# shield_radio-comand.net
KiCad netlist of a schematic drawn in EAGLE
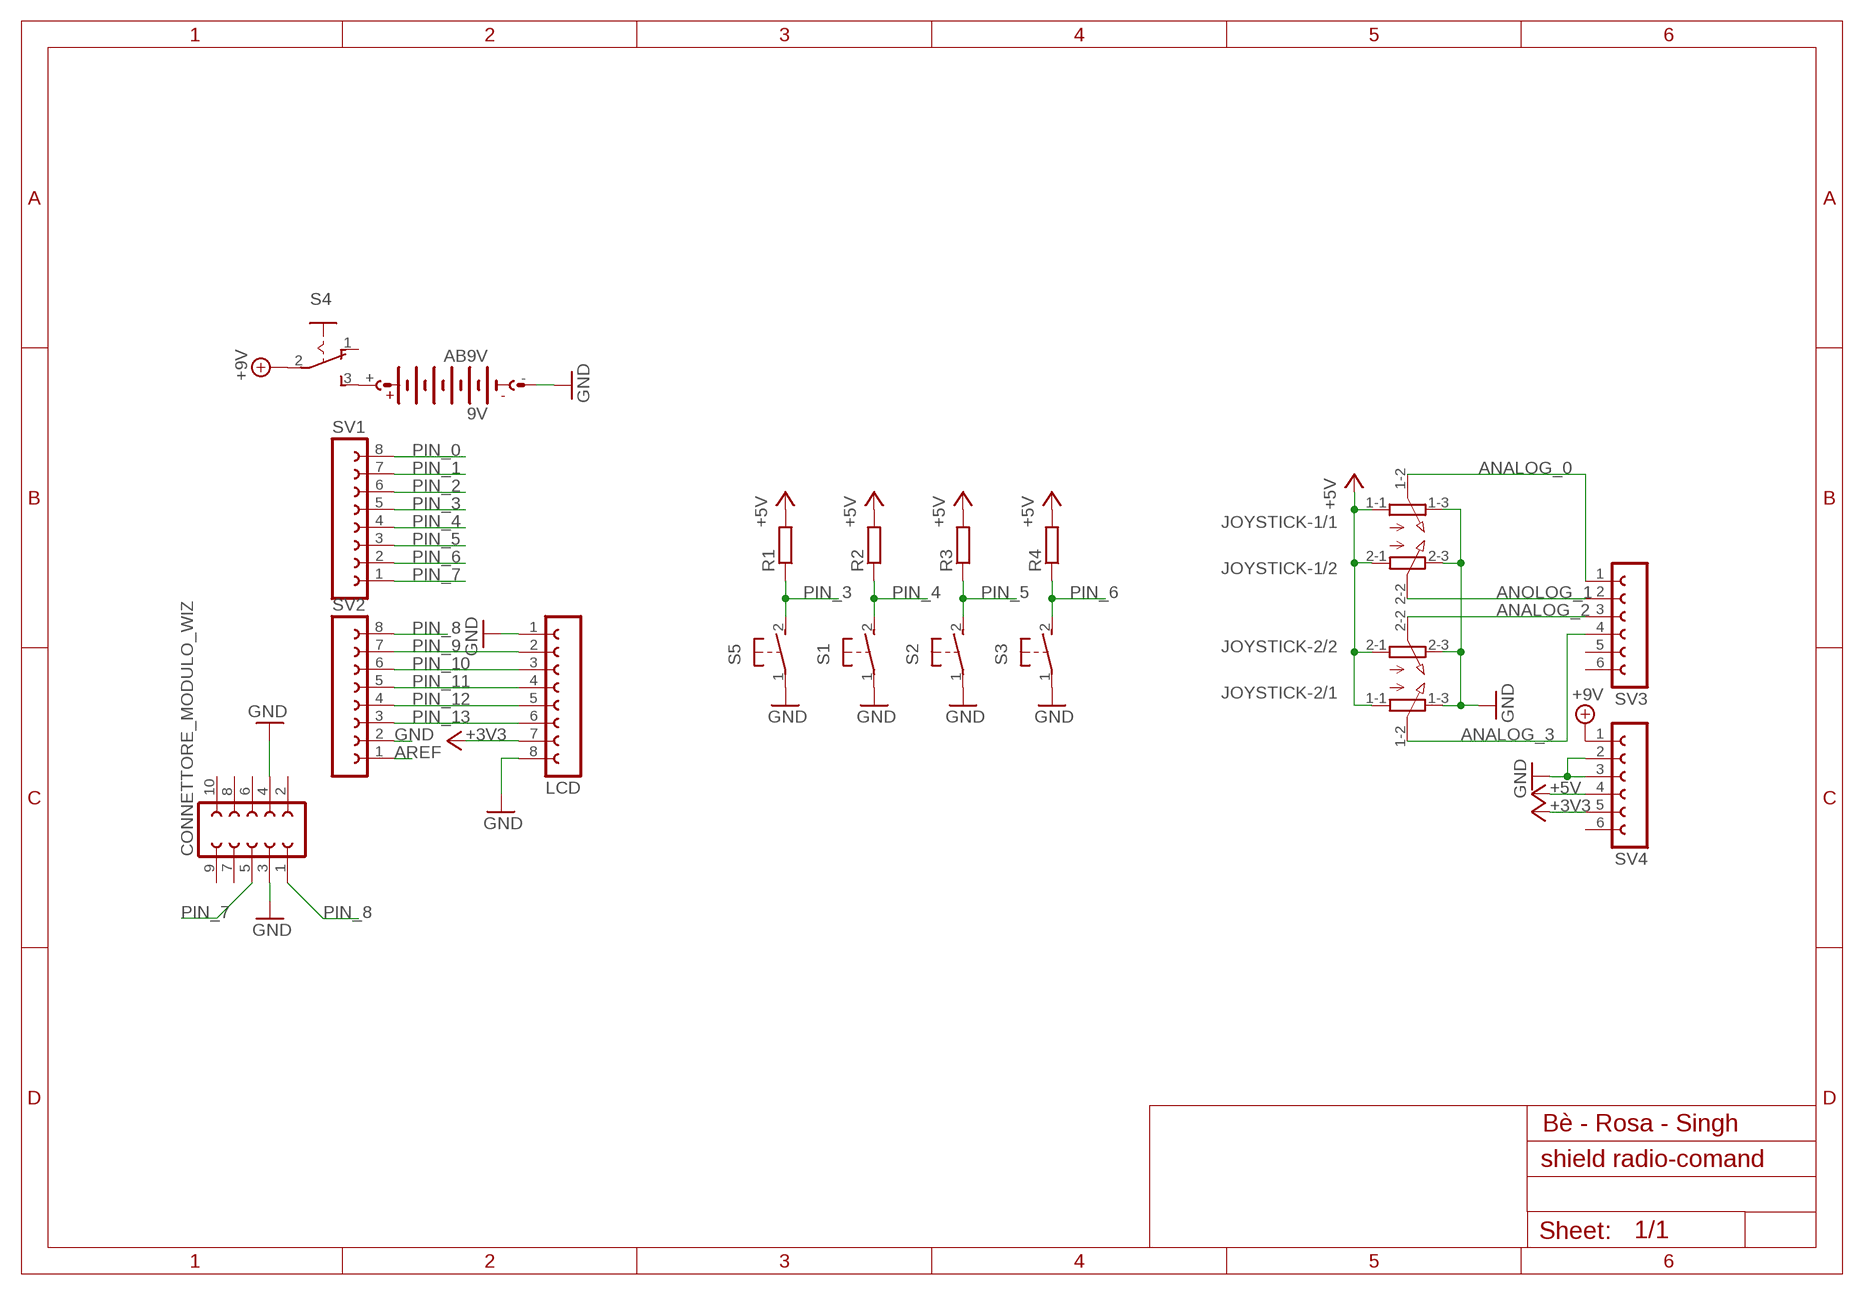
[diagram p0: schematic, sheet 1]

(export (version "E")
  (design (tool "Eeschema 10.0.6"))
  (components
    (comp (ref "9V")
      (value "AB9V")
      (footprint "eagle-import:AB9V")
      (libsource (lib "eagle-import") (part "AB9V"))
    )
    (comp (ref "CONNETTORE_MODULO_WIZ")
      (value "FE05-2")
      (footprint "eagle-import:FE05-2")
      (libsource (lib "eagle-import") (part "FE05-2"))
    )
    (comp (ref "JOYSTICK-1")
      (value "3RP/1610G")
      (footprint "eagle-import:3RP_1610G")
      (libsource (lib "eagle-import") (part "3RP/1610G"))
    )
    (comp (ref "JOYSTICK-2")
      (value "3RP/1610G")
      (footprint "eagle-import:3RP_1610G")
      (libsource (lib "eagle-import") (part "3RP/1610G"))
    )
    (comp (ref "LCD")
      (value "FE08-1")
      (footprint "eagle-import:FE08")
      (libsource (lib "eagle-import") (part "FE08-1"))
    )
    (comp (ref "R1")
      (value "R-EU_0207/10")
      (footprint "eagle-import:0207_10")
      (libsource (lib "eagle-import") (part "R-EU_0207/10"))
    )
    (comp (ref "R2")
      (value "R-EU_0207/10")
      (footprint "eagle-import:0207_10")
      (libsource (lib "eagle-import") (part "R-EU_0207/10"))
    )
    (comp (ref "R3")
      (value "R-EU_0207/10")
      (footprint "eagle-import:0207_10")
      (libsource (lib "eagle-import") (part "R-EU_0207/10"))
    )
    (comp (ref "R4")
      (value "R-EU_0207/10")
      (footprint "eagle-import:0207_10")
      (libsource (lib "eagle-import") (part "R-EU_0207/10"))
    )
    (comp (ref "S1")
      (value "31-XX")
      (footprint "eagle-import:B3F-31XX")
      (fields (field (name "MPN") "B3F-3100"))
      (libsource (lib "eagle-import") (part "31-XX"))
    )
    (comp (ref "S2")
      (value "31-XX")
      (footprint "eagle-import:B3F-31XX")
      (fields (field (name "MPN") "B3F-3100"))
      (libsource (lib "eagle-import") (part "31-XX"))
    )
    (comp (ref "S3")
      (value "31-XX")
      (footprint "eagle-import:B3F-31XX")
      (fields (field (name "MPN") "B3F-3100"))
      (libsource (lib "eagle-import") (part "31-XX"))
    )
    (comp (ref "S4")
      (value "255SB")
      (footprint "eagle-import:255SB")
      (libsource (lib "eagle-import") (part "255SB"))
    )
    (comp (ref "S5")
      (value "31-XX")
      (footprint "eagle-import:B3F-31XX")
      (fields (field (name "MPN") "B3F-3100"))
      (libsource (lib "eagle-import") (part "31-XX"))
    )
    (comp (ref "SV1")
      (value "FE08-1")
      (footprint "eagle-import:FE08")
      (libsource (lib "eagle-import") (part "FE08-1"))
    )
    (comp (ref "SV2")
      (value "FE08-1")
      (footprint "eagle-import:FE08")
      (libsource (lib "eagle-import") (part "FE08-1"))
    )
    (comp (ref "SV3")
      (value "FE06-1")
      (footprint "eagle-import:FE06")
      (libsource (lib "eagle-import") (part "FE06-1"))
    )
    (comp (ref "SV4")
      (value "FE06-1")
      (footprint "eagle-import:FE06")
      (libsource (lib "eagle-import") (part "FE06-1"))
    )
  )
  (nets
    (net (code "1") (name "+3V3") (class "Default")
      (node (ref "LCD") (pin "7") (pinfunction "7_7") (pintype "passive"))
      (node (ref "SV4") (pin "5") (pinfunction "5_5") (pintype "passive"))
    )
    (net (code "2") (name "+5V") (class "Default")
      (node (ref "JOYSTICK-1") (pin "1-1") (pinfunction "A_1-1") (pintype "passive"))
      (node (ref "JOYSTICK-1") (pin "2-1") (pinfunction "A_2-1") (pintype "passive"))
      (node (ref "JOYSTICK-2") (pin "1-1") (pinfunction "A_1-1") (pintype "passive"))
      (node (ref "JOYSTICK-2") (pin "2-1") (pinfunction "A_2-1") (pintype "passive"))
      (node (ref "R1") (pin "2") (pinfunction "2_2") (pintype "passive"))
      (node (ref "R2") (pin "2") (pinfunction "2_2") (pintype "passive"))
      (node (ref "R3") (pin "2") (pinfunction "2_2") (pintype "passive"))
      (node (ref "R4") (pin "2") (pinfunction "2_2") (pintype "passive"))
      (node (ref "SV4") (pin "4") (pinfunction "4_4") (pintype "passive"))
    )
    (net (code "3") (name "+9V") (class "Default")
      (node (ref "S4") (pin "2") (pinfunction "P_2") (pintype "passive"))
      (node (ref "SV4") (pin "1") (pinfunction "1_1") (pintype "passive"))
    )
    (net (code "4") (name "/ANALOG_0") (class "Default")
      (node (ref "JOYSTICK-1") (pin "1-2") (pinfunction "S_1-2") (pintype "passive"))
      (node (ref "SV3") (pin "1") (pinfunction "1_1") (pintype "passive"))
    )
    (net (code "5") (name "/ANALOG_2") (class "Default")
      (node (ref "JOYSTICK-2") (pin "2-2") (pinfunction "S_2-2") (pintype "passive"))
      (node (ref "SV3") (pin "3") (pinfunction "3_3") (pintype "passive"))
    )
    (net (code "6") (name "/ANALOG_3") (class "Default")
      (node (ref "JOYSTICK-2") (pin "1-2") (pinfunction "S_1-2") (pintype "passive"))
      (node (ref "SV3") (pin "4") (pinfunction "4_4") (pintype "passive"))
    )
    (net (code "7") (name "/ANOLOG_1") (class "Default")
      (node (ref "JOYSTICK-1") (pin "2-2") (pinfunction "S_2-2") (pintype "passive"))
      (node (ref "SV3") (pin "2") (pinfunction "2_2") (pintype "passive"))
    )
    (net (code "8") (name "/AREF") (class "Default")
      (node (ref "SV2") (pin "1") (pinfunction "1_1") (pintype "passive"))
    )
    (net (code "9") (name "/PIN_0") (class "Default")
      (node (ref "SV1") (pin "8") (pinfunction "8_8") (pintype "passive"))
    )
    (net (code "10") (name "/PIN_1") (class "Default")
      (node (ref "SV1") (pin "7") (pinfunction "7_7") (pintype "passive"))
    )
    (net (code "11") (name "/PIN_2") (class "Default")
      (node (ref "SV1") (pin "6") (pinfunction "6_6") (pintype "passive"))
    )
    (net (code "12") (name "/PIN_3") (class "Default")
      (node (ref "R1") (pin "1") (pinfunction "1_1") (pintype "passive"))
      (node (ref "S5") (pin "2") (pinfunction "S_2") (pintype "passive"))
      (node (ref "SV1") (pin "5") (pinfunction "5_5") (pintype "passive"))
    )
    (net (code "13") (name "/PIN_4") (class "Default")
      (node (ref "R2") (pin "1") (pinfunction "1_1") (pintype "passive"))
      (node (ref "S1") (pin "2") (pinfunction "S_2") (pintype "passive"))
      (node (ref "SV1") (pin "4") (pinfunction "4_4") (pintype "passive"))
    )
    (net (code "14") (name "/PIN_5") (class "Default")
      (node (ref "R3") (pin "1") (pinfunction "1_1") (pintype "passive"))
      (node (ref "S2") (pin "2") (pinfunction "S_2") (pintype "passive"))
      (node (ref "SV1") (pin "3") (pinfunction "3_3") (pintype "passive"))
    )
    (net (code "15") (name "/PIN_6") (class "Default")
      (node (ref "R4") (pin "1") (pinfunction "1_1") (pintype "passive"))
      (node (ref "S3") (pin "2") (pinfunction "S_2") (pintype "passive"))
      (node (ref "SV1") (pin "2") (pinfunction "2_2") (pintype "passive"))
    )
    (net (code "16") (name "/PIN_7") (class "Default")
      (node (ref "CONNETTORE_MODULO_WIZ") (pin "5") (pinfunction "5_5") (pintype "passive"))
      (node (ref "SV1") (pin "1") (pinfunction "1_1") (pintype "passive"))
    )
    (net (code "17") (name "/PIN_8") (class "Default")
      (node (ref "CONNETTORE_MODULO_WIZ") (pin "1") (pinfunction "1_1") (pintype "passive"))
      (node (ref "SV2") (pin "8") (pinfunction "8_8") (pintype "passive"))
    )
    (net (code "18") (name "/PIN_9") (class "Default")
      (node (ref "LCD") (pin "2") (pinfunction "2_2") (pintype "passive"))
      (node (ref "SV2") (pin "7") (pinfunction "7_7") (pintype "passive"))
    )
    (net (code "19") (name "/PIN_10") (class "Default")
      (node (ref "LCD") (pin "3") (pinfunction "3_3") (pintype "passive"))
      (node (ref "SV2") (pin "6") (pinfunction "6_6") (pintype "passive"))
    )
    (net (code "20") (name "/PIN_11") (class "Default")
      (node (ref "LCD") (pin "4") (pinfunction "4_4") (pintype "passive"))
      (node (ref "SV2") (pin "5") (pinfunction "5_5") (pintype "passive"))
    )
    (net (code "21") (name "/PIN_12") (class "Default")
      (node (ref "LCD") (pin "5") (pinfunction "5_5") (pintype "passive"))
      (node (ref "SV2") (pin "4") (pinfunction "4_4") (pintype "passive"))
    )
    (net (code "22") (name "/PIN_13") (class "Default")
      (node (ref "LCD") (pin "6") (pinfunction "6_6") (pintype "passive"))
      (node (ref "SV2") (pin "3") (pinfunction "3_3") (pintype "passive"))
    )
    (net (code "23") (name "GND") (class "Default")
      (node (ref "9V") (pin "-") (pinfunction "-_-") (pintype "passive"))
      (node (ref "CONNETTORE_MODULO_WIZ") (pin "3") (pinfunction "3_3") (pintype "passive"))
      (node (ref "CONNETTORE_MODULO_WIZ") (pin "4") (pinfunction "4_4") (pintype "passive"))
      (node (ref "JOYSTICK-1") (pin "1-3") (pinfunction "E_1-3") (pintype "passive"))
      (node (ref "JOYSTICK-1") (pin "2-3") (pinfunction "E_2-3") (pintype "passive"))
      (node (ref "JOYSTICK-2") (pin "1-3") (pinfunction "E_1-3") (pintype "passive"))
      (node (ref "JOYSTICK-2") (pin "2-3") (pinfunction "E_2-3") (pintype "passive"))
      (node (ref "LCD") (pin "1") (pinfunction "1_1") (pintype "passive"))
      (node (ref "LCD") (pin "8") (pinfunction "8_8") (pintype "passive"))
      (node (ref "S1") (pin "1") (pinfunction "P_1") (pintype "passive"))
      (node (ref "S2") (pin "1") (pinfunction "P_1") (pintype "passive"))
      (node (ref "S3") (pin "1") (pinfunction "P_1") (pintype "passive"))
      (node (ref "S5") (pin "1") (pinfunction "P_1") (pintype "passive"))
      (node (ref "SV2") (pin "2") (pinfunction "2_2") (pintype "passive"))
      (node (ref "SV4") (pin "2") (pinfunction "2_2") (pintype "passive"))
      (node (ref "SV4") (pin "3") (pinfunction "3_3") (pintype "passive"))
    )
    (net (code "24") (name "Net-(S4-S)") (class "Default")
      (node (ref "9V") (pin "+") (pinfunction "+_+") (pintype "passive"))
      (node (ref "S4") (pin "3") (pinfunction "S_3") (pintype "passive"))
    )
    (net (code "25") (name "unconnected-(CONNETTORE_MODULO_WIZ-Pad2)") (class "Default")
      (node (ref "CONNETTORE_MODULO_WIZ") (pin "2") (pinfunction "2_2") (pintype "passive"))
    )
    (net (code "26") (name "unconnected-(CONNETTORE_MODULO_WIZ-Pad6)") (class "Default")
      (node (ref "CONNETTORE_MODULO_WIZ") (pin "6") (pinfunction "6_6") (pintype "passive"))
    )
    (net (code "27") (name "unconnected-(CONNETTORE_MODULO_WIZ-Pad7)") (class "Default")
      (node (ref "CONNETTORE_MODULO_WIZ") (pin "7") (pinfunction "7_7") (pintype "passive"))
    )
    (net (code "28") (name "unconnected-(CONNETTORE_MODULO_WIZ-Pad8)") (class "Default")
      (node (ref "CONNETTORE_MODULO_WIZ") (pin "8") (pinfunction "8_8") (pintype "passive"))
    )
    (net (code "29") (name "unconnected-(CONNETTORE_MODULO_WIZ-Pad9)") (class "Default")
      (node (ref "CONNETTORE_MODULO_WIZ") (pin "9") (pinfunction "9_9") (pintype "passive"))
    )
    (net (code "30") (name "unconnected-(CONNETTORE_MODULO_WIZ-Pad10)") (class "Default")
      (node (ref "CONNETTORE_MODULO_WIZ") (pin "10") (pinfunction "10_10") (pintype "passive"))
    )
    (net (code "31") (name "unconnected-(S4-O-Pad1)") (class "Default")
      (node (ref "S4") (pin "1") (pinfunction "O_1") (pintype "passive"))
    )
    (net (code "32") (name "unconnected-(SV3-Pad5)") (class "Default")
      (node (ref "SV3") (pin "5") (pinfunction "5_5") (pintype "passive"))
    )
    (net (code "33") (name "unconnected-(SV3-Pad6)") (class "Default")
      (node (ref "SV3") (pin "6") (pinfunction "6_6") (pintype "passive"))
    )
    (net (code "34") (name "unconnected-(SV4-Pad6)") (class "Default")
      (node (ref "SV4") (pin "6") (pinfunction "6_6") (pintype "passive"))
    )
  )
)
